# powermeter.net
KiCad netlist of a schematic drawn in EAGLE
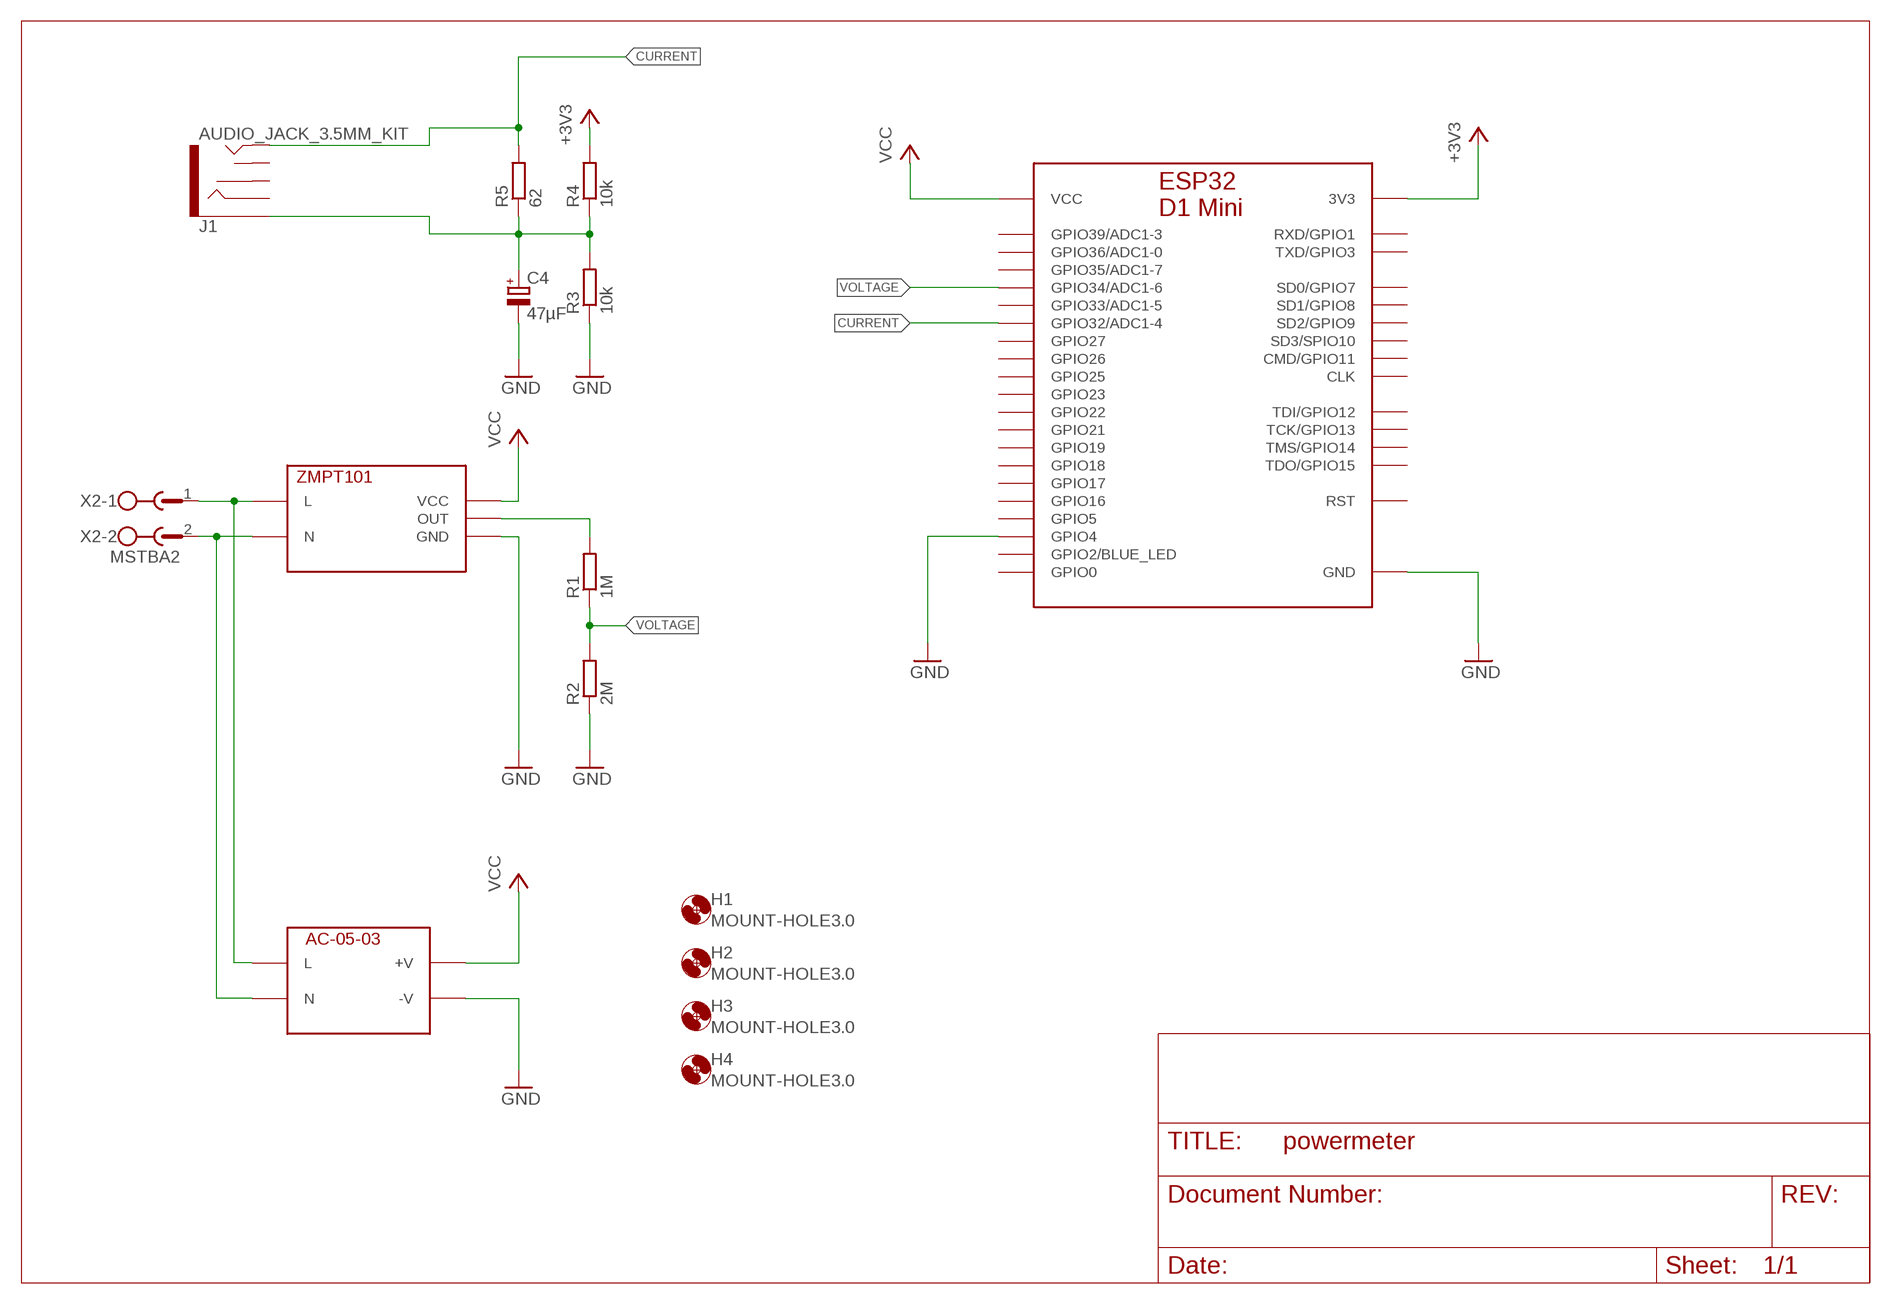
[diagram p0: schematic, sheet 1]

(export (version "E")
  (design (tool "Eeschema 10.0.6"))
  (components
    (comp (ref "C4")
      (value "47µF")
      (footprint "eagle-import:E2,5-5")
      (libsource (lib "eagle-import") (part "CPOL-EUE2.5-5"))
    )
    (comp (ref "H1")
      (value "MOUNT-HOLE3.0")
      (footprint "eagle-import:3,0")
      (libsource (lib "eagle-import") (part "MOUNT-HOLE3.0"))
    )
    (comp (ref "H2")
      (value "MOUNT-HOLE3.0")
      (footprint "eagle-import:3,0")
      (libsource (lib "eagle-import") (part "MOUNT-HOLE3.0"))
    )
    (comp (ref "H3")
      (value "MOUNT-HOLE3.0")
      (footprint "eagle-import:3,0")
      (libsource (lib "eagle-import") (part "MOUNT-HOLE3.0"))
    )
    (comp (ref "H4")
      (value "MOUNT-HOLE3.0")
      (footprint "eagle-import:3,0")
      (libsource (lib "eagle-import") (part "MOUNT-HOLE3.0"))
    )
    (comp (ref "J1")
      (value "AUDIO_JACK_3.5MM_KIT")
      (footprint "eagle-import:AUDIO-JACK-KIT")
      (libsource (lib "eagle-import") (part "AUDIO_JACK_3.5MM_KIT"))
    )
    (comp (ref "R1")
      (value "1M")
      (footprint "eagle-import:0204_7")
      (libsource (lib "eagle-import") (part "R-EU_0204/7"))
    )
    (comp (ref "R2")
      (value "2M")
      (footprint "eagle-import:0204_7")
      (libsource (lib "eagle-import") (part "R-EU_0204/7"))
    )
    (comp (ref "R3")
      (value "10k")
      (footprint "eagle-import:0204_7")
      (libsource (lib "eagle-import") (part "R-EU_0204/7"))
    )
    (comp (ref "R4")
      (value "10k")
      (footprint "eagle-import:0204_7")
      (libsource (lib "eagle-import") (part "R-EU_0204/7"))
    )
    (comp (ref "R5")
      (value "62")
      (footprint "eagle-import:0204_7")
      (libsource (lib "eagle-import") (part "R-EU_0204/7"))
    )
    (comp (ref "U$1")
      (value "ZMPT101")
      (footprint "eagle-import:ZMPT101")
      (libsource (lib "eagle-import") (part "ZMPT101"))
    )
    (comp (ref "U$2")
      (value "AC-05-03")
      (footprint "eagle-import:AC-05-03")
      (libsource (lib "eagle-import") (part "AC-05-03"))
    )
    (comp (ref "U1")
      (value "ESP32D1MINI")
      (footprint "eagle-import:ESP32D1MINI")
      (libsource (lib "eagle-import") (part "ESP32D1MINI"))
    )
    (comp (ref "X2")
      (value "MSTBA2")
      (footprint "eagle-import:MSTBA2")
      (fields (field (name "MF") "FARNELL") (field (name "MPN") "1757242"))
      (libsource (lib "eagle-import") (part "MSTBA2"))
    )
  )
  (nets
    (net (code "1") (name "+3V3") (class "Default")
      (node (ref "R4") (pin "2") (pinfunction "2_2") (pintype "passive"))
      (node (ref "U1") (pin "3V3") (pinfunction "3V3_3V3") (pintype "power_in"))
    )
    (net (code "2") (name "CURRENT") (class "Default")
      (node (ref "J1") (pin "TIP") (pinfunction "TIP_TIP") (pintype "bidirectional"))
      (node (ref "R5") (pin "2") (pinfunction "2_2") (pintype "passive"))
      (node (ref "U1") (pin "IO32") (pinfunction "GPIO32/ADC1-4_IO32") (pintype "bidirectional"))
    )
    (net (code "3") (name "GND") (class "Default")
      (node (ref "C4") (pin "-") (pinfunction "-_-") (pintype "passive"))
      (node (ref "R2") (pin "1") (pinfunction "1_1") (pintype "passive"))
      (node (ref "R3") (pin "1") (pinfunction "1_1") (pintype "passive"))
      (node (ref "U$1") (pin "P$3") (pinfunction "GND_P$3") (pintype "power_in"))
      (node (ref "U$1") (pin "P$4") (pinfunction "GND_P$4") (pintype "power_in"))
      (node (ref "U$2") (pin "-V") (pinfunction "-V_-V") (pintype "output"))
      (node (ref "U1") (pin "GND1") (pinfunction "GND_GND1") (pintype "power_in"))
      (node (ref "U1") (pin "GND2") (pinfunction "GND_GND2") (pintype "power_in"))
      (node (ref "U1") (pin "GND3") (pinfunction "GND_GND3") (pintype "power_in"))
      (node (ref "U1") (pin "IO4") (pinfunction "GPIO4_IO4") (pintype "bidirectional"))
    )
    (net (code "4") (name "Net-(C4-Pad+)") (class "Default")
      (node (ref "C4") (pin "+") (pinfunction "+_+") (pintype "passive"))
      (node (ref "J1") (pin "SLEEVE") (pinfunction "SLEEVE_SLEEVE") (pintype "bidirectional"))
      (node (ref "R3") (pin "2") (pinfunction "2_2") (pintype "passive"))
      (node (ref "R4") (pin "1") (pinfunction "1_1") (pintype "passive"))
      (node (ref "R5") (pin "1") (pinfunction "1_1") (pintype "passive"))
    )
    (net (code "5") (name "Net-(R1-Pad2)") (class "Default")
      (node (ref "R1") (pin "2") (pinfunction "2_2") (pintype "passive"))
      (node (ref "U$1") (pin "OUT") (pinfunction "OUT_OUT") (pintype "output"))
    )
    (net (code "6") (name "Net-(U$1-PadL)") (class "Default")
      (node (ref "U$1") (pin "L") (pinfunction "L_L") (pintype "input"))
      (node (ref "U$2") (pin "L") (pinfunction "L_L") (pintype "input"))
      (node (ref "X2") (pin "1") (pinfunction "1_1") (pintype "passive"))
    )
    (net (code "7") (name "Net-(X2B-1)") (class "Default")
      (node (ref "U$1") (pin "N") (pinfunction "N_N") (pintype "input"))
      (node (ref "U$2") (pin "N") (pinfunction "N_N") (pintype "input"))
      (node (ref "X2") (pin "2") (pinfunction "1_2") (pintype "passive"))
    )
    (net (code "8") (name "VCC") (class "Default")
      (node (ref "U$1") (pin "VCC") (pinfunction "VCC_VCC") (pintype "power_in"))
      (node (ref "U$2") (pin "+V") (pinfunction "+V_+V") (pintype "output"))
      (node (ref "U1") (pin "VCC") (pinfunction "VCC_VCC") (pintype "power_in"))
    )
    (net (code "9") (name "VOLTAGE") (class "Default")
      (node (ref "R1") (pin "1") (pinfunction "1_1") (pintype "passive"))
      (node (ref "R2") (pin "2") (pinfunction "2_2") (pintype "passive"))
      (node (ref "U1") (pin "IO34") (pinfunction "GPIO34/ADC1-6_IO34") (pintype "bidirectional"))
    )
    (net (code "10") (name "unconnected-(J1-PadRING)") (class "Default")
      (node (ref "J1") (pin "RING") (pinfunction "RING_RING") (pintype "bidirectional"))
    )
    (net (code "11") (name "unconnected-(J1-PadRSH)") (class "Default")
      (node (ref "J1") (pin "RSH") (pinfunction "RSH_RSH") (pintype "bidirectional"))
    )
    (net (code "12") (name "unconnected-(J1-PadTSH)") (class "Default")
      (node (ref "J1") (pin "TSH") (pinfunction "TSH_TSH") (pintype "bidirectional"))
    )
    (net (code "13") (name "unconnected-(U1-CMD{slash}GPIO11-PadCMD)") (class "Default")
      (node (ref "U1") (pin "CMD") (pinfunction "CMD/GPIO11_CMD") (pintype "bidirectional"))
    )
    (net (code "14") (name "unconnected-(U1-GPIO0-PadIO0)") (class "Default")
      (node (ref "U1") (pin "IO0") (pinfunction "GPIO0_IO0") (pintype "input"))
    )
    (net (code "15") (name "unconnected-(U1-GPIO2{slash}BLUE_LED-PadIO2)") (class "Default")
      (node (ref "U1") (pin "IO2") (pinfunction "GPIO2/BLUE_LED_IO2") (pintype "bidirectional"))
    )
    (net (code "16") (name "unconnected-(U1-GPIO5-PadIO5)") (class "Default")
      (node (ref "U1") (pin "IO5") (pinfunction "GPIO5_IO5") (pintype "bidirectional"))
    )
    (net (code "17") (name "unconnected-(U1-GPIO16-PadIO16)") (class "Default")
      (node (ref "U1") (pin "IO16") (pinfunction "GPIO16_IO16") (pintype "bidirectional"))
    )
    (net (code "18") (name "unconnected-(U1-GPIO17-PadIO17)") (class "Default")
      (node (ref "U1") (pin "IO17") (pinfunction "GPIO17_IO17") (pintype "bidirectional"))
    )
    (net (code "19") (name "unconnected-(U1-GPIO18-PadIO18)") (class "Default")
      (node (ref "U1") (pin "IO18") (pinfunction "GPIO18_IO18") (pintype "bidirectional"))
    )
    (net (code "20") (name "unconnected-(U1-GPIO19-PadIO19)") (class "Default")
      (node (ref "U1") (pin "IO19") (pinfunction "GPIO19_IO19") (pintype "bidirectional"))
    )
    (net (code "21") (name "unconnected-(U1-GPIO21-PadIO21)") (class "Default")
      (node (ref "U1") (pin "IO21") (pinfunction "GPIO21_IO21") (pintype "bidirectional"))
    )
    (net (code "22") (name "unconnected-(U1-GPIO22-PadIO22)") (class "Default")
      (node (ref "U1") (pin "IO22") (pinfunction "GPIO22_IO22") (pintype "bidirectional"))
    )
    (net (code "23") (name "unconnected-(U1-GPIO23-PadIO23)") (class "Default")
      (node (ref "U1") (pin "IO23") (pinfunction "GPIO23_IO23") (pintype "bidirectional"))
    )
    (net (code "24") (name "unconnected-(U1-GPIO25-PadIO25)") (class "Default")
      (node (ref "U1") (pin "IO25") (pinfunction "GPIO25_IO25") (pintype "bidirectional"))
    )
    (net (code "25") (name "unconnected-(U1-GPIO26-PadIO26)") (class "Default")
      (node (ref "U1") (pin "IO26") (pinfunction "GPIO26_IO26") (pintype "bidirectional"))
    )
    (net (code "26") (name "unconnected-(U1-GPIO27-PadIO27)") (class "Default")
      (node (ref "U1") (pin "IO27") (pinfunction "GPIO27_IO27") (pintype "bidirectional"))
    )
    (net (code "27") (name "unconnected-(U1-GPIO33{slash}ADC1-5-PadIO33)") (class "Default")
      (node (ref "U1") (pin "IO33") (pinfunction "GPIO33/ADC1-5_IO33") (pintype "bidirectional"))
    )
    (net (code "28") (name "unconnected-(U1-GPIO35{slash}ADC1-7-PadIO35)") (class "Default")
      (node (ref "U1") (pin "IO35") (pinfunction "GPIO35/ADC1-7_IO35") (pintype "bidirectional"))
    )
    (net (code "29") (name "unconnected-(U1-GPIO36{slash}ADC1-0-PadIO36)") (class "Default")
      (node (ref "U1") (pin "IO36") (pinfunction "GPIO36/ADC1-0_IO36") (pintype "bidirectional"))
    )
    (net (code "30") (name "unconnected-(U1-GPIO39{slash}ADC1-3-PadIO39)") (class "Default")
      (node (ref "U1") (pin "IO39") (pinfunction "GPIO39/ADC1-3_IO39") (pintype "bidirectional"))
    )
    (net (code "31") (name "unconnected-(U1-PadCLK)") (class "Default")
      (node (ref "U1") (pin "CLK") (pinfunction "CLK_CLK") (pintype "bidirectional"))
    )
    (net (code "32") (name "unconnected-(U1-PadRST)") (class "Default")
      (node (ref "U1") (pin "RST") (pinfunction "RST_RST") (pintype "input"))
    )
    (net (code "33") (name "unconnected-(U1-RXD{slash}GPIO1-PadRXD)") (class "Default")
      (node (ref "U1") (pin "RXD") (pinfunction "RXD/GPIO1_RXD") (pintype "input"))
    )
    (net (code "34") (name "unconnected-(U1-SD0{slash}GPIO7-PadSD0)") (class "Default")
      (node (ref "U1") (pin "SD0") (pinfunction "SD0/GPIO7_SD0") (pintype "bidirectional"))
    )
    (net (code "35") (name "unconnected-(U1-SD1{slash}GPIO8-PadSD1)") (class "Default")
      (node (ref "U1") (pin "SD1") (pinfunction "SD1/GPIO8_SD1") (pintype "bidirectional"))
    )
    (net (code "36") (name "unconnected-(U1-SD2{slash}GPIO9-PadSD2)") (class "Default")
      (node (ref "U1") (pin "SD2") (pinfunction "SD2/GPIO9_SD2") (pintype "bidirectional"))
    )
    (net (code "37") (name "unconnected-(U1-SD3{slash}SPIO10-PadSD3)") (class "Default")
      (node (ref "U1") (pin "SD3") (pinfunction "SD3/SPIO10_SD3") (pintype "bidirectional"))
    )
    (net (code "38") (name "unconnected-(U1-TCK{slash}GPIO13-PadTCK)") (class "Default")
      (node (ref "U1") (pin "TCK") (pinfunction "TCK/GPIO13_TCK") (pintype "bidirectional"))
    )
    (net (code "39") (name "unconnected-(U1-TDI{slash}GPIO12-PadTDI)") (class "Default")
      (node (ref "U1") (pin "TDI") (pinfunction "TDI/GPIO12_TDI") (pintype "bidirectional"))
    )
    (net (code "40") (name "unconnected-(U1-TDO{slash}GPIO15-PadTDO)") (class "Default")
      (node (ref "U1") (pin "TDO") (pinfunction "TDO/GPIO15_TDO") (pintype "bidirectional"))
    )
    (net (code "41") (name "unconnected-(U1-TMS{slash}GPIO14-PadTMS)") (class "Default")
      (node (ref "U1") (pin "TMS") (pinfunction "TMS/GPIO14_TMS") (pintype "bidirectional"))
    )
    (net (code "42") (name "unconnected-(U1-TXD{slash}GPIO3-PadTXD)") (class "Default")
      (node (ref "U1") (pin "TXD") (pinfunction "TXD/GPIO3_TXD") (pintype "bidirectional"))
    )
  )
)
